# 2_-INTERFACE_CONNS.net
KiCad netlist of a schematic drawn in Altium Designer
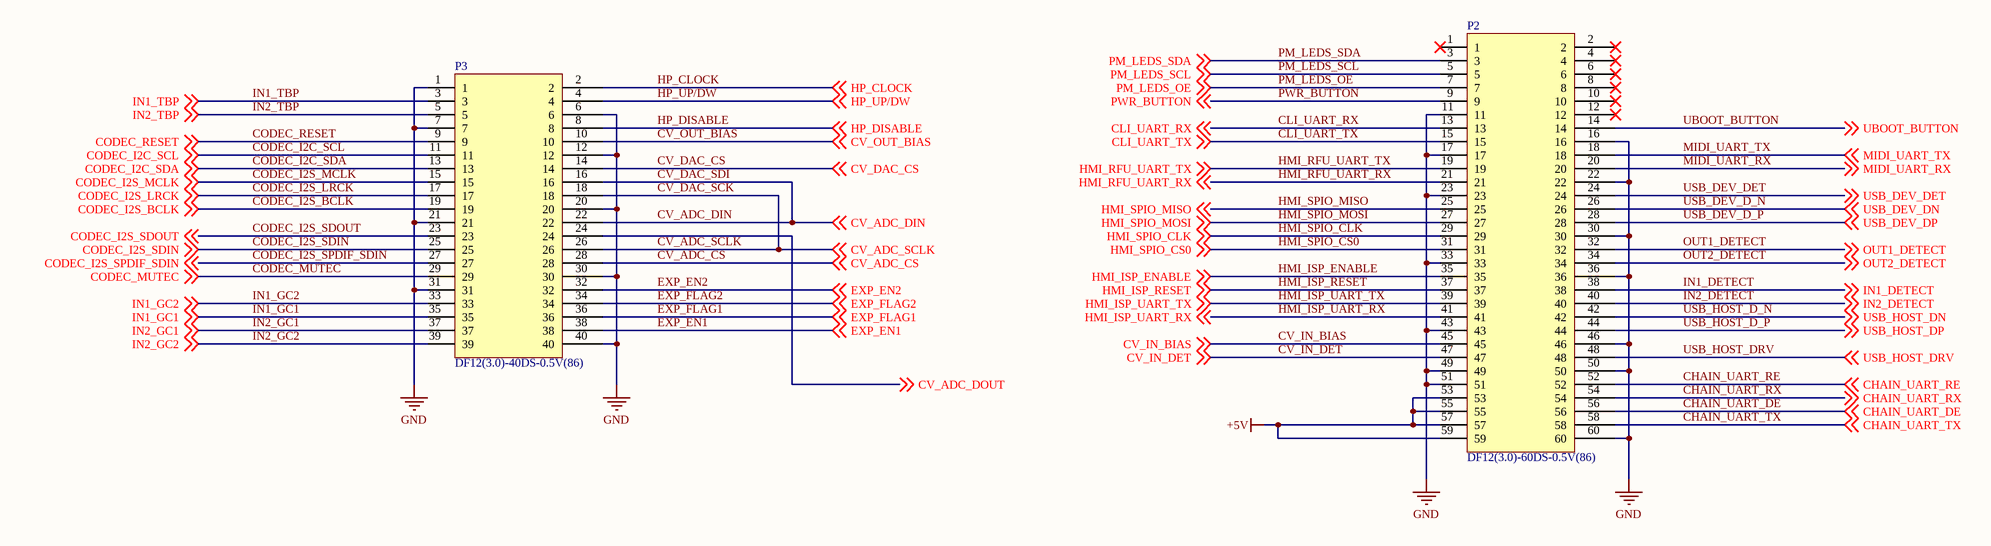
[diagram p0: [2]-INTERFACE_CONNS.SchDoc]

(export (version "E")
  (design (tool "Eeschema 10.0.6"))
  (components
    (comp (ref "P2")
      (value "DF12(3.0)-60DS-0.5V(86)")
      (footprint "DF12-60")
      (description "CONN RECEPT 60POS 3MM SMD 0.5MM")
      (libsource (lib "bitsnio") (part "DF12(3.0)-60DS-0.5V(86)"))
    )
    (comp (ref "P3")
      (value "DF12(3.0)-40DS-0.5V(86)")
      (footprint "DF12-40")
      (description "CONN RECEPT 40POS 3MM SMD 0.5MM")
      (libsource (lib "bitsnio") (part "DF12(3.0)-40DS-0.5V(86)"))
    )
  )
  (nets
    (net (code "1") (name "+5V") (class "Default")
      (node (ref "P2") (pin "53") (pinfunction "53_53") (pintype "passive"))
      (node (ref "P2") (pin "55") (pinfunction "55_55") (pintype "passive"))
      (node (ref "P2") (pin "57") (pinfunction "57_57") (pintype "passive"))
      (node (ref "P2") (pin "59") (pinfunction "59_59") (pintype "passive"))
    )
    (net (code "2") (name "CHAIN_UART_DE") (class "Default")
      (node (ref "P2") (pin "56") (pinfunction "56_56") (pintype "passive"))
    )
    (net (code "3") (name "CHAIN_UART_RE") (class "Default")
      (node (ref "P2") (pin "52") (pinfunction "52_52") (pintype "passive"))
    )
    (net (code "4") (name "CHAIN_UART_RX") (class "Default")
      (node (ref "P2") (pin "54") (pinfunction "54_54") (pintype "passive"))
    )
    (net (code "5") (name "CHAIN_UART_TX") (class "Default")
      (node (ref "P2") (pin "58") (pinfunction "58_58") (pintype "passive"))
    )
    (net (code "6") (name "CLI_UART_RX") (class "Default")
      (node (ref "P2") (pin "13") (pinfunction "13_13") (pintype "passive"))
    )
    (net (code "7") (name "CLI_UART_TX") (class "Default")
      (node (ref "P2") (pin "15") (pinfunction "15_15") (pintype "passive"))
    )
    (net (code "8") (name "CODEC_I2C_SCL") (class "Default")
      (node (ref "P3") (pin "11") (pinfunction "11_11") (pintype "passive"))
    )
    (net (code "9") (name "CODEC_I2C_SDA") (class "Default")
      (node (ref "P3") (pin "13") (pinfunction "13_13") (pintype "passive"))
    )
    (net (code "10") (name "CODEC_I2S_BCLK") (class "Default")
      (node (ref "P3") (pin "19") (pinfunction "19_19") (pintype "passive"))
    )
    (net (code "11") (name "CODEC_I2S_LRCK") (class "Default")
      (node (ref "P3") (pin "17") (pinfunction "17_17") (pintype "passive"))
    )
    (net (code "12") (name "CODEC_I2S_MCLK") (class "Default")
      (node (ref "P3") (pin "15") (pinfunction "15_15") (pintype "passive"))
    )
    (net (code "13") (name "CODEC_I2S_SDIN") (class "Default")
      (node (ref "P3") (pin "25") (pinfunction "25_25") (pintype "passive"))
    )
    (net (code "14") (name "CODEC_I2S_SDOUT") (class "Default")
      (node (ref "P3") (pin "23") (pinfunction "23_23") (pintype "passive"))
    )
    (net (code "15") (name "CODEC_I2S_SPDIF_SDIN") (class "Default")
      (node (ref "P3") (pin "27") (pinfunction "27_27") (pintype "passive"))
    )
    (net (code "16") (name "CODEC_MUTEC") (class "Default")
      (node (ref "P3") (pin "29") (pinfunction "29_29") (pintype "passive"))
    )
    (net (code "17") (name "CODEC_RESET") (class "Default")
      (node (ref "P3") (pin "9") (pinfunction "9_9") (pintype "passive"))
    )
    (net (code "18") (name "CV_ADC_CS") (class "Default")
      (node (ref "P3") (pin "28") (pinfunction "28_28") (pintype "passive"))
    )
    (net (code "19") (name "CV_ADC_DIN") (class "Default")
      (node (ref "P3") (pin "16") (pinfunction "16_16") (pintype "passive"))
      (node (ref "P3") (pin "22") (pinfunction "22_22") (pintype "passive"))
    )
    (net (code "20") (name "CV_ADC_DOUT") (class "Default")
      (node (ref "P3") (pin "24") (pinfunction "24_24") (pintype "passive"))
    )
    (net (code "21") (name "CV_ADC_SCLK") (class "Default")
      (node (ref "P3") (pin "18") (pinfunction "18_18") (pintype "passive"))
      (node (ref "P3") (pin "26") (pinfunction "26_26") (pintype "passive"))
    )
    (net (code "22") (name "CV_DAC_CS") (class "Default")
      (node (ref "P3") (pin "14") (pinfunction "14_14") (pintype "passive"))
    )
    (net (code "23") (name "CV_IN_BIAS") (class "Default")
      (node (ref "P2") (pin "45") (pinfunction "45_45") (pintype "passive"))
    )
    (net (code "24") (name "CV_IN_DET") (class "Default")
      (node (ref "P2") (pin "47") (pinfunction "47_47") (pintype "passive"))
    )
    (net (code "25") (name "CV_OUT_BIAS") (class "Default")
      (node (ref "P3") (pin "10") (pinfunction "10_10") (pintype "passive"))
    )
    (net (code "26") (name "EXP_EN1") (class "Default")
      (node (ref "P3") (pin "38") (pinfunction "38_38") (pintype "passive"))
    )
    (net (code "27") (name "EXP_EN2") (class "Default")
      (node (ref "P3") (pin "32") (pinfunction "32_32") (pintype "passive"))
    )
    (net (code "28") (name "EXP_FLAG1") (class "Default")
      (node (ref "P3") (pin "36") (pinfunction "36_36") (pintype "passive"))
    )
    (net (code "29") (name "EXP_FLAG2") (class "Default")
      (node (ref "P3") (pin "34") (pinfunction "34_34") (pintype "passive"))
    )
    (net (code "30") (name "GND") (class "Default")
      (node (ref "P2") (pin "11") (pinfunction "11_11") (pintype "passive"))
      (node (ref "P2") (pin "16") (pinfunction "16_16") (pintype "passive"))
      (node (ref "P2") (pin "17") (pinfunction "17_17") (pintype "passive"))
      (node (ref "P2") (pin "22") (pinfunction "22_22") (pintype "passive"))
      (node (ref "P2") (pin "23") (pinfunction "23_23") (pintype "passive"))
      (node (ref "P2") (pin "30") (pinfunction "30_30") (pintype "passive"))
      (node (ref "P2") (pin "33") (pinfunction "33_33") (pintype "passive"))
      (node (ref "P2") (pin "36") (pinfunction "36_36") (pintype "passive"))
      (node (ref "P2") (pin "43") (pinfunction "43_43") (pintype "passive"))
      (node (ref "P2") (pin "46") (pinfunction "46_46") (pintype "passive"))
      (node (ref "P2") (pin "49") (pinfunction "49_49") (pintype "passive"))
      (node (ref "P2") (pin "50") (pinfunction "50_50") (pintype "passive"))
      (node (ref "P2") (pin "51") (pinfunction "51_51") (pintype "passive"))
      (node (ref "P2") (pin "60") (pinfunction "60_60") (pintype "passive"))
      (node (ref "P3") (pin "1") (pinfunction "1_1") (pintype "passive"))
      (node (ref "P3") (pin "12") (pinfunction "12_12") (pintype "passive"))
      (node (ref "P3") (pin "20") (pinfunction "20_20") (pintype "passive"))
      (node (ref "P3") (pin "21") (pinfunction "21_21") (pintype "passive"))
      (node (ref "P3") (pin "30") (pinfunction "30_30") (pintype "passive"))
      (node (ref "P3") (pin "31") (pinfunction "31_31") (pintype "passive"))
      (node (ref "P3") (pin "40") (pinfunction "40_40") (pintype "passive"))
      (node (ref "P3") (pin "6") (pinfunction "6_6") (pintype "passive"))
      (node (ref "P3") (pin "7") (pinfunction "7_7") (pintype "passive"))
    )
    (net (code "31") (name "HMI_ISP_ENABLE") (class "Default")
      (node (ref "P2") (pin "35") (pinfunction "35_35") (pintype "passive"))
    )
    (net (code "32") (name "HMI_ISP_RESET") (class "Default")
      (node (ref "P2") (pin "37") (pinfunction "37_37") (pintype "passive"))
    )
    (net (code "33") (name "HMI_ISP_UART_RX") (class "Default")
      (node (ref "P2") (pin "41") (pinfunction "41_41") (pintype "passive"))
    )
    (net (code "34") (name "HMI_ISP_UART_TX") (class "Default")
      (node (ref "P2") (pin "39") (pinfunction "39_39") (pintype "passive"))
    )
    (net (code "35") (name "HMI_RFU_UART_RX") (class "Default")
      (node (ref "P2") (pin "21") (pinfunction "21_21") (pintype "passive"))
    )
    (net (code "36") (name "HMI_RFU_UART_TX") (class "Default")
      (node (ref "P2") (pin "19") (pinfunction "19_19") (pintype "passive"))
    )
    (net (code "37") (name "HMI_SPIO_CLK") (class "Default")
      (node (ref "P2") (pin "29") (pinfunction "29_29") (pintype "passive"))
    )
    (net (code "38") (name "HMI_SPIO_CS0") (class "Default")
      (node (ref "P2") (pin "31") (pinfunction "31_31") (pintype "passive"))
    )
    (net (code "39") (name "HMI_SPIO_MISO") (class "Default")
      (node (ref "P2") (pin "25") (pinfunction "25_25") (pintype "passive"))
    )
    (net (code "40") (name "HMI_SPIO_MOSI") (class "Default")
      (node (ref "P2") (pin "27") (pinfunction "27_27") (pintype "passive"))
    )
    (net (code "41") (name "HP_CLOCK") (class "Default")
      (node (ref "P3") (pin "2") (pinfunction "2_2") (pintype "passive"))
    )
    (net (code "42") (name "HP_DISABLE") (class "Default")
      (node (ref "P3") (pin "8") (pinfunction "8_8") (pintype "passive"))
    )
    (net (code "43") (name "HP_UP{slash}DW") (class "Default")
      (node (ref "P3") (pin "4") (pinfunction "4_4") (pintype "passive"))
    )
    (net (code "44") (name "IN1_DETECT") (class "Default")
      (node (ref "P2") (pin "38") (pinfunction "38_38") (pintype "passive"))
    )
    (net (code "45") (name "IN1_GC1") (class "Default")
      (node (ref "P3") (pin "35") (pinfunction "35_35") (pintype "passive"))
    )
    (net (code "46") (name "IN1_GC2") (class "Default")
      (node (ref "P3") (pin "33") (pinfunction "33_33") (pintype "passive"))
    )
    (net (code "47") (name "IN1_TBP") (class "Default")
      (node (ref "P3") (pin "3") (pinfunction "3_3") (pintype "passive"))
    )
    (net (code "48") (name "IN2_DETECT") (class "Default")
      (node (ref "P2") (pin "40") (pinfunction "40_40") (pintype "passive"))
    )
    (net (code "49") (name "IN2_GC1") (class "Default")
      (node (ref "P3") (pin "37") (pinfunction "37_37") (pintype "passive"))
    )
    (net (code "50") (name "IN2_GC2") (class "Default")
      (node (ref "P3") (pin "39") (pinfunction "39_39") (pintype "passive"))
    )
    (net (code "51") (name "IN2_TBP") (class "Default")
      (node (ref "P3") (pin "5") (pinfunction "5_5") (pintype "passive"))
    )
    (net (code "52") (name "MIDI_UART_RX") (class "Default")
      (node (ref "P2") (pin "20") (pinfunction "20_20") (pintype "passive"))
    )
    (net (code "53") (name "MIDI_UART_TX") (class "Default")
      (node (ref "P2") (pin "18") (pinfunction "18_18") (pintype "passive"))
    )
    (net (code "54") (name "OUT1_DETECT") (class "Default")
      (node (ref "P2") (pin "32") (pinfunction "32_32") (pintype "passive"))
    )
    (net (code "55") (name "OUT2_DETECT") (class "Default")
      (node (ref "P2") (pin "34") (pinfunction "34_34") (pintype "passive"))
    )
    (net (code "56") (name "PM_LEDS_OE") (class "Default")
      (node (ref "P2") (pin "7") (pinfunction "7_7") (pintype "passive"))
    )
    (net (code "57") (name "PM_LEDS_SCL") (class "Default")
      (node (ref "P2") (pin "5") (pinfunction "5_5") (pintype "passive"))
    )
    (net (code "58") (name "PM_LEDS_SDA") (class "Default")
      (node (ref "P2") (pin "3") (pinfunction "3_3") (pintype "passive"))
    )
    (net (code "59") (name "PWR_BUTTON") (class "Default")
      (node (ref "P2") (pin "9") (pinfunction "9_9") (pintype "passive"))
    )
    (net (code "60") (name "UBOOT_BUTTON") (class "Default")
      (node (ref "P2") (pin "14") (pinfunction "14_14") (pintype "passive"))
    )
    (net (code "61") (name "USB_DEV_DET") (class "Default")
      (node (ref "P2") (pin "24") (pinfunction "24_24") (pintype "passive"))
    )
    (net (code "62") (name "USB_DEV_DN") (class "Default")
      (node (ref "P2") (pin "26") (pinfunction "26_26") (pintype "passive"))
    )
    (net (code "63") (name "USB_DEV_DP") (class "Default")
      (node (ref "P2") (pin "28") (pinfunction "28_28") (pintype "passive"))
    )
    (net (code "64") (name "USB_HOST_DN") (class "Default")
      (node (ref "P2") (pin "42") (pinfunction "42_42") (pintype "passive"))
    )
    (net (code "65") (name "USB_HOST_DP") (class "Default")
      (node (ref "P2") (pin "44") (pinfunction "44_44") (pintype "passive"))
    )
    (net (code "66") (name "USB_HOST_DRV") (class "Default")
      (node (ref "P2") (pin "48") (pinfunction "48_48") (pintype "passive"))
    )
    (net (code "67") (name "unconnected-(P2-Pad1)") (class "Default")
      (node (ref "P2") (pin "1") (pinfunction "1_1") (pintype "passive+no_connect"))
    )
    (net (code "68") (name "unconnected-(P2-Pad2)") (class "Default")
      (node (ref "P2") (pin "2") (pinfunction "2_2") (pintype "passive+no_connect"))
    )
    (net (code "69") (name "unconnected-(P2-Pad4)") (class "Default")
      (node (ref "P2") (pin "4") (pinfunction "4_4") (pintype "passive+no_connect"))
    )
    (net (code "70") (name "unconnected-(P2-Pad6)") (class "Default")
      (node (ref "P2") (pin "6") (pinfunction "6_6") (pintype "passive+no_connect"))
    )
    (net (code "71") (name "unconnected-(P2-Pad8)") (class "Default")
      (node (ref "P2") (pin "8") (pinfunction "8_8") (pintype "passive+no_connect"))
    )
    (net (code "72") (name "unconnected-(P2-Pad10)") (class "Default")
      (node (ref "P2") (pin "10") (pinfunction "10_10") (pintype "passive+no_connect"))
    )
    (net (code "73") (name "unconnected-(P2-Pad12)") (class "Default")
      (node (ref "P2") (pin "12") (pinfunction "12_12") (pintype "passive+no_connect"))
    )
  )
)
